# BPU_display-v1d_2-28inch.net
KiCad netlist of a schematic drawn in EAGLE
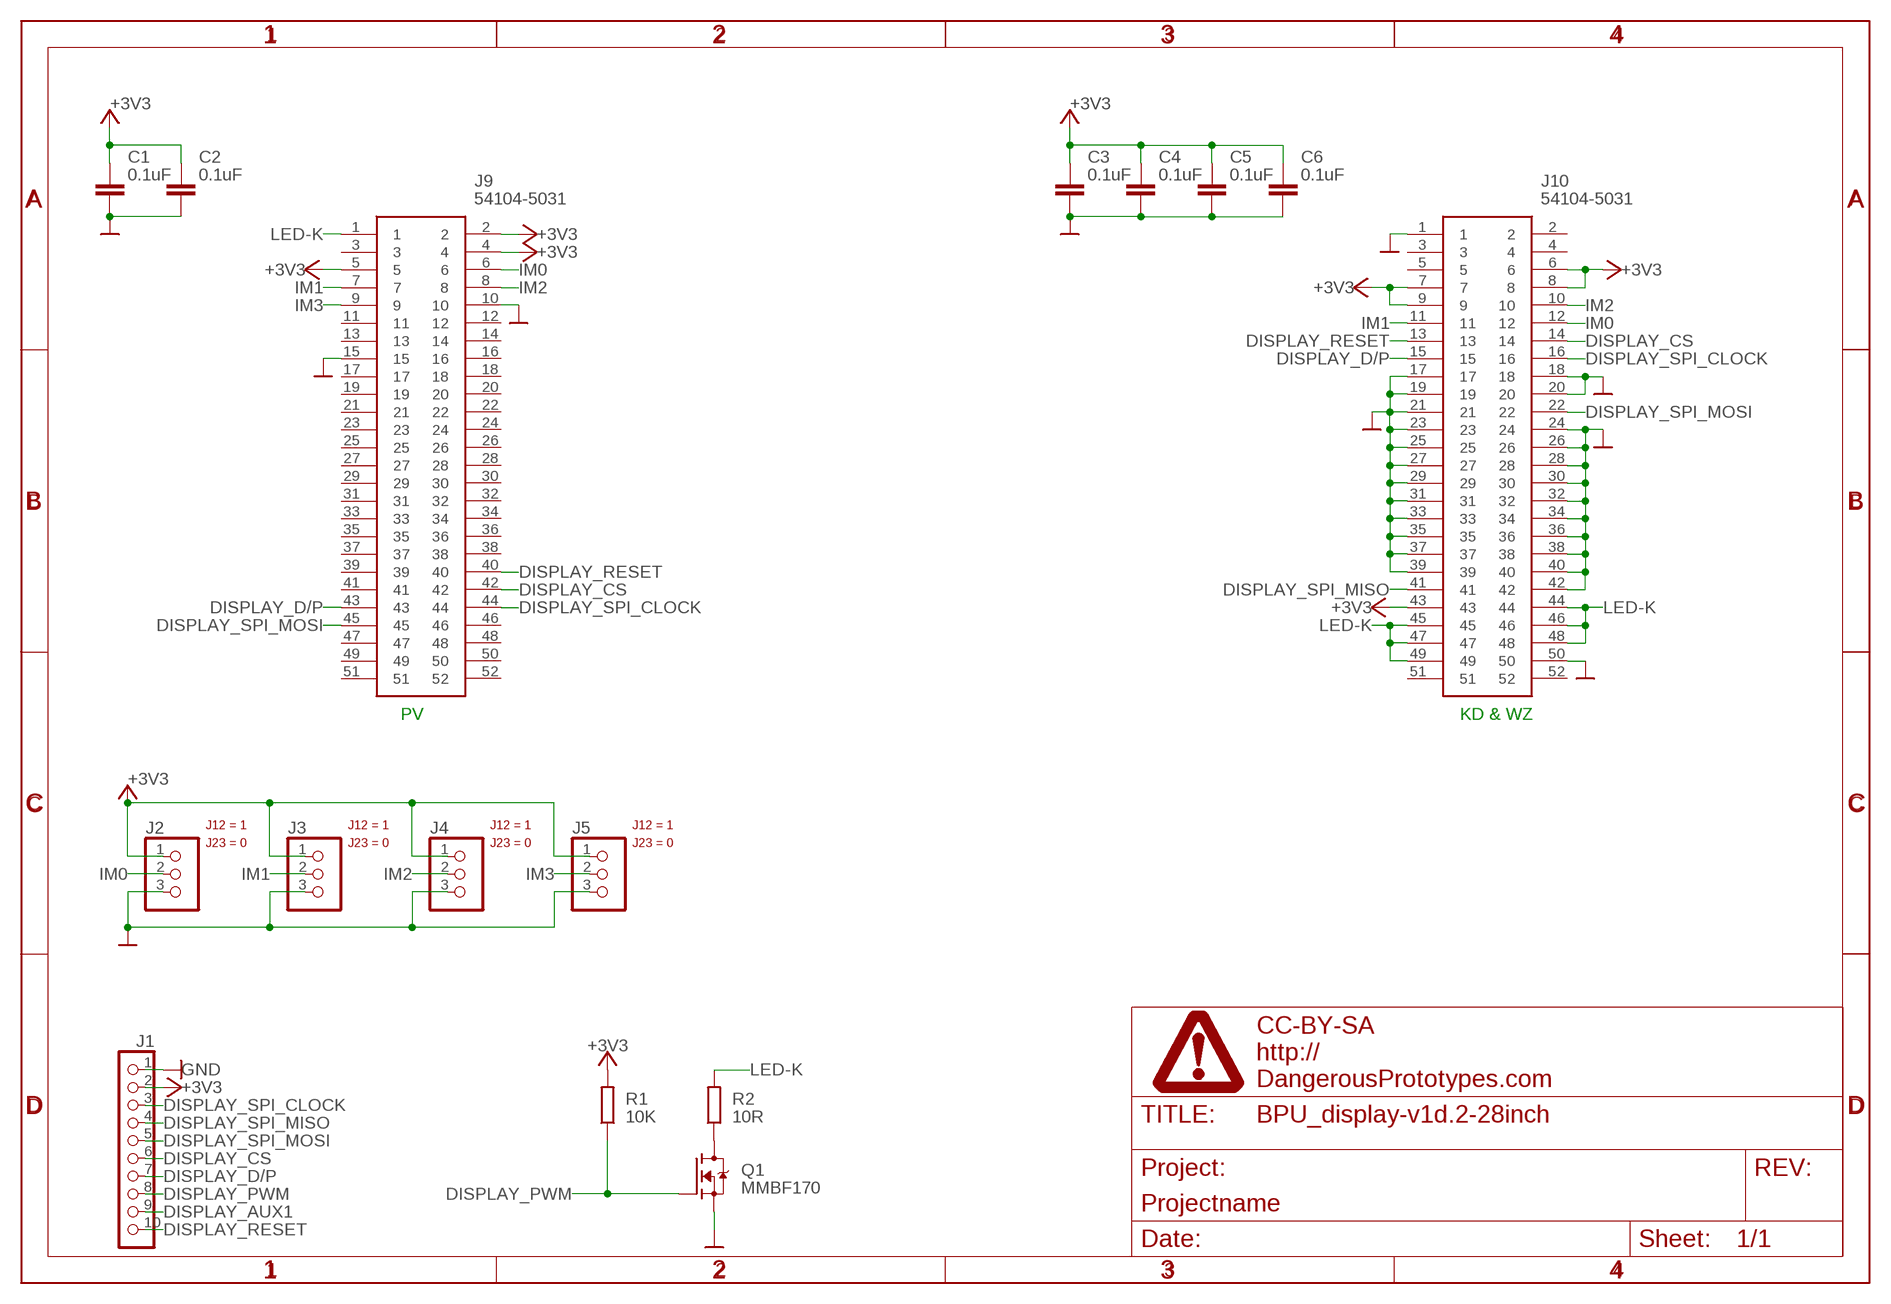
[diagram p0: schematic, sheet 1]

(export (version "E")
  (design (tool "Eeschema 10.0.6"))
  (components
    (comp (ref "C1")
      (value "0.1uF")
      (footprint "eagle-import:C603")
      (libsource (lib "eagle-import") (part "CAPACITOR_NPOL-0603"))
    )
    (comp (ref "C2")
      (value "0.1uF")
      (footprint "eagle-import:C603")
      (libsource (lib "eagle-import") (part "CAPACITOR_NPOL-0603"))
    )
    (comp (ref "C3")
      (value "0.1uF")
      (footprint "eagle-import:C603")
      (libsource (lib "eagle-import") (part "CAPACITOR_NPOL-0603"))
    )
    (comp (ref "C4")
      (value "0.1uF")
      (footprint "eagle-import:C603")
      (libsource (lib "eagle-import") (part "CAPACITOR_NPOL-0603"))
    )
    (comp (ref "C5")
      (value "0.1uF")
      (footprint "eagle-import:C603")
      (libsource (lib "eagle-import") (part "CAPACITOR_NPOL-0603"))
    )
    (comp (ref "C6")
      (value "0.1uF")
      (footprint "eagle-import:C603")
      (libsource (lib "eagle-import") (part "CAPACITOR_NPOL-0603"))
    )
    (comp (ref "J1")
      (value "CON-FPC_X05B20L10T")
      (footprint "eagle-import:X05B20L10T")
      (libsource (lib "eagle-import") (part "CON-FPC_X05B20L10T"))
    )
    (comp (ref "J2")
      (value "JUMPER_1X30805")
      (footprint "eagle-import:JP3_0805")
      (fields
        (field (name "J12") "optA")
        (field (name "J23") "optB")
        (field (name "J12_1") "1")
        (field (name "J23_1") "0")
      )
      (libsource (lib "eagle-import") (part "JUMPER_1X30805"))
    )
    (comp (ref "J3")
      (value "JUMPER_1X30805")
      (footprint "eagle-import:JP3_0805")
      (fields
        (field (name "J12") "optA")
        (field (name "J23") "optB")
        (field (name "J12_1") "1")
        (field (name "J23_1") "0")
      )
      (libsource (lib "eagle-import") (part "JUMPER_1X30805"))
    )
    (comp (ref "J4")
      (value "JUMPER_1X30805")
      (footprint "eagle-import:JP3_0805")
      (fields
        (field (name "J12") "optA")
        (field (name "J23") "optB")
        (field (name "J12_1") "1")
        (field (name "J23_1") "0")
      )
      (libsource (lib "eagle-import") (part "JUMPER_1X30805"))
    )
    (comp (ref "J5")
      (value "JUMPER_1X30805")
      (footprint "eagle-import:JP3_0805")
      (fields
        (field (name "J12") "optA")
        (field (name "J23") "optB")
        (field (name "J12_1") "1")
        (field (name "J23_1") "0")
      )
      (libsource (lib "eagle-import") (part "JUMPER_1X30805"))
    )
    (comp (ref "J9")
      (value "54104-5031")
      (footprint "eagle-import:541045031")
      (fields (field (name "MOUSER_PART_NUMBER") "538-54104-5031"))
      (libsource (lib "eagle-import") (part "54104-5031"))
    )
    (comp (ref "J10")
      (value "54104-5031")
      (footprint "eagle-import:541045031")
      (fields (field (name "MOUSER_PART_NUMBER") "538-54104-5031"))
      (libsource (lib "eagle-import") (part "54104-5031"))
    )
    (comp (ref "PAGE1")
      (value "FRAME_DINA4_L")
      (footprint "eagle-import:DP_LOGO")
      (fields
        (field (name "LICENSE") "CC-BY-SA")
        (field (name "URL1") "http://")
        (field (name "URL2") "DangerousPrototypes.com")
        (field (name "PROJECT") "Projectname")
      )
      (libsource (lib "eagle-import") (part "FRAME_DINA4_L"))
    )
    (comp (ref "Q1")
      (value "MMBF170")
      (footprint "eagle-import:SOT-23")
      (libsource (lib "eagle-import") (part "TRANSISTOR_FET_BS170-SOT-23"))
    )
    (comp (ref "R1")
      (value "10K")
      (footprint "eagle-import:R0603")
      (libsource (lib "eagle-import") (part "R-EU_R0603"))
    )
    (comp (ref "R2")
      (value "10R")
      (footprint "eagle-import:R0603")
      (libsource (lib "eagle-import") (part "R-EU_R0603"))
    )
  )
  (nets
    (net (code "1") (name "/DISPLAY_AUX1") (class "Default")
      (node (ref "J1") (pin "9") (pinfunction "9_9") (pintype "passive"))
    )
    (net (code "2") (name "/DISPLAY_CS") (class "Default")
      (node (ref "J1") (pin "6") (pinfunction "6_6") (pintype "passive"))
      (node (ref "J10") (pin "14") (pinfunction "14_14") (pintype "bidirectional"))
      (node (ref "J9") (pin "42") (pinfunction "42_42") (pintype "bidirectional"))
    )
    (net (code "3") (name "/DISPLAY_D{slash}P") (class "Default")
      (node (ref "J1") (pin "7") (pinfunction "7_7") (pintype "passive"))
      (node (ref "J10") (pin "15") (pinfunction "15_15") (pintype "bidirectional"))
      (node (ref "J9") (pin "43") (pinfunction "43_43") (pintype "bidirectional"))
    )
    (net (code "4") (name "/DISPLAY_PWM") (class "Default")
      (node (ref "J1") (pin "8") (pinfunction "8_8") (pintype "passive"))
      (node (ref "Q1") (pin "1") (pinfunction "G_1") (pintype "passive"))
      (node (ref "R1") (pin "1") (pinfunction "1_1") (pintype "passive"))
    )
    (net (code "5") (name "/DISPLAY_RESET") (class "Default")
      (node (ref "J1") (pin "10") (pinfunction "10_10") (pintype "passive"))
      (node (ref "J10") (pin "13") (pinfunction "13_13") (pintype "bidirectional"))
      (node (ref "J9") (pin "40") (pinfunction "40_40") (pintype "bidirectional"))
    )
    (net (code "6") (name "/DISPLAY_SPI_CLOCK") (class "Default")
      (node (ref "J1") (pin "3") (pinfunction "3_3") (pintype "passive"))
      (node (ref "J10") (pin "16") (pinfunction "16_16") (pintype "bidirectional"))
      (node (ref "J9") (pin "44") (pinfunction "44_44") (pintype "bidirectional"))
    )
    (net (code "7") (name "/DISPLAY_SPI_MISO") (class "Default")
      (node (ref "J1") (pin "4") (pinfunction "4_4") (pintype "passive"))
      (node (ref "J10") (pin "41") (pinfunction "41_41") (pintype "bidirectional"))
    )
    (net (code "8") (name "/DISPLAY_SPI_MOSI") (class "Default")
      (node (ref "J1") (pin "5") (pinfunction "5_5") (pintype "passive"))
      (node (ref "J10") (pin "22") (pinfunction "22_22") (pintype "bidirectional"))
      (node (ref "J9") (pin "45") (pinfunction "45_45") (pintype "bidirectional"))
    )
    (net (code "9") (name "/IM0") (class "Default")
      (node (ref "J10") (pin "12") (pinfunction "12_12") (pintype "bidirectional"))
      (node (ref "J2") (pin "2") (pinfunction "2_2") (pintype "passive"))
      (node (ref "J9") (pin "6") (pinfunction "6_6") (pintype "bidirectional"))
    )
    (net (code "10") (name "/IM1") (class "Default")
      (node (ref "J10") (pin "11") (pinfunction "11_11") (pintype "bidirectional"))
      (node (ref "J3") (pin "2") (pinfunction "2_2") (pintype "passive"))
      (node (ref "J9") (pin "7") (pinfunction "7_7") (pintype "bidirectional"))
    )
    (net (code "11") (name "/IM2") (class "Default")
      (node (ref "J10") (pin "10") (pinfunction "10_10") (pintype "bidirectional"))
      (node (ref "J4") (pin "2") (pinfunction "2_2") (pintype "passive"))
      (node (ref "J9") (pin "8") (pinfunction "8_8") (pintype "bidirectional"))
    )
    (net (code "12") (name "/IM3") (class "Default")
      (node (ref "J5") (pin "2") (pinfunction "2_2") (pintype "passive"))
      (node (ref "J9") (pin "9") (pinfunction "9_9") (pintype "bidirectional"))
    )
    (net (code "13") (name "/LED-K") (class "Default")
      (node (ref "J10") (pin "44") (pinfunction "44_44") (pintype "bidirectional"))
      (node (ref "J10") (pin "45") (pinfunction "45_45") (pintype "bidirectional"))
      (node (ref "J10") (pin "46") (pinfunction "46_46") (pintype "bidirectional"))
      (node (ref "J10") (pin "47") (pinfunction "47_47") (pintype "bidirectional"))
      (node (ref "J10") (pin "48") (pinfunction "48_48") (pintype "bidirectional"))
      (node (ref "J10") (pin "49") (pinfunction "49_49") (pintype "bidirectional"))
      (node (ref "J9") (pin "1") (pinfunction "1_1") (pintype "bidirectional"))
      (node (ref "R2") (pin "2") (pinfunction "2_2") (pintype "passive"))
    )
    (net (code "14") (name "Net-(Q1-D)") (class "Default")
      (node (ref "Q1") (pin "3") (pinfunction "D_3") (pintype "passive"))
      (node (ref "R2") (pin "1") (pinfunction "1_1") (pintype "passive"))
    )
    (net (code "15") (name "SUPPLY_+3V3") (class "Default")
      (node (ref "C1") (pin "1") (pinfunction "1_1") (pintype "passive"))
      (node (ref "C2") (pin "1") (pinfunction "1_1") (pintype "passive"))
      (node (ref "C3") (pin "1") (pinfunction "1_1") (pintype "passive"))
      (node (ref "C4") (pin "1") (pinfunction "1_1") (pintype "passive"))
      (node (ref "C5") (pin "1") (pinfunction "1_1") (pintype "passive"))
      (node (ref "C6") (pin "1") (pinfunction "1_1") (pintype "passive"))
      (node (ref "J1") (pin "2") (pinfunction "2_2") (pintype "passive"))
      (node (ref "J10") (pin "43") (pinfunction "43_43") (pintype "bidirectional"))
      (node (ref "J10") (pin "6") (pinfunction "6_6") (pintype "bidirectional"))
      (node (ref "J10") (pin "7") (pinfunction "7_7") (pintype "bidirectional"))
      (node (ref "J10") (pin "8") (pinfunction "8_8") (pintype "bidirectional"))
      (node (ref "J10") (pin "9") (pinfunction "9_9") (pintype "bidirectional"))
      (node (ref "J2") (pin "1") (pinfunction "1_1") (pintype "passive"))
      (node (ref "J3") (pin "1") (pinfunction "1_1") (pintype "passive"))
      (node (ref "J4") (pin "1") (pinfunction "1_1") (pintype "passive"))
      (node (ref "J5") (pin "1") (pinfunction "1_1") (pintype "passive"))
      (node (ref "J9") (pin "2") (pinfunction "2_2") (pintype "bidirectional"))
      (node (ref "J9") (pin "4") (pinfunction "4_4") (pintype "bidirectional"))
      (node (ref "J9") (pin "5") (pinfunction "5_5") (pintype "bidirectional"))
      (node (ref "R1") (pin "2") (pinfunction "2_2") (pintype "passive"))
    )
    (net (code "16") (name "SUPPLY_GND") (class "Default")
      (node (ref "C1") (pin "2") (pinfunction "2_2") (pintype "passive"))
      (node (ref "C2") (pin "2") (pinfunction "2_2") (pintype "passive"))
      (node (ref "C3") (pin "2") (pinfunction "2_2") (pintype "passive"))
      (node (ref "C4") (pin "2") (pinfunction "2_2") (pintype "passive"))
      (node (ref "C5") (pin "2") (pinfunction "2_2") (pintype "passive"))
      (node (ref "C6") (pin "2") (pinfunction "2_2") (pintype "passive"))
      (node (ref "J1") (pin "1") (pinfunction "1_1") (pintype "passive"))
      (node (ref "J10") (pin "1") (pinfunction "1_1") (pintype "bidirectional"))
      (node (ref "J10") (pin "17") (pinfunction "17_17") (pintype "bidirectional"))
      (node (ref "J10") (pin "18") (pinfunction "18_18") (pintype "bidirectional"))
      (node (ref "J10") (pin "19") (pinfunction "19_19") (pintype "bidirectional"))
      (node (ref "J10") (pin "20") (pinfunction "20_20") (pintype "bidirectional"))
      (node (ref "J10") (pin "21") (pinfunction "21_21") (pintype "bidirectional"))
      (node (ref "J10") (pin "23") (pinfunction "23_23") (pintype "bidirectional"))
      (node (ref "J10") (pin "24") (pinfunction "24_24") (pintype "bidirectional"))
      (node (ref "J10") (pin "25") (pinfunction "25_25") (pintype "bidirectional"))
      (node (ref "J10") (pin "26") (pinfunction "26_26") (pintype "bidirectional"))
      (node (ref "J10") (pin "27") (pinfunction "27_27") (pintype "bidirectional"))
      (node (ref "J10") (pin "28") (pinfunction "28_28") (pintype "bidirectional"))
      (node (ref "J10") (pin "29") (pinfunction "29_29") (pintype "bidirectional"))
      (node (ref "J10") (pin "30") (pinfunction "30_30") (pintype "bidirectional"))
      (node (ref "J10") (pin "31") (pinfunction "31_31") (pintype "bidirectional"))
      (node (ref "J10") (pin "32") (pinfunction "32_32") (pintype "bidirectional"))
      (node (ref "J10") (pin "33") (pinfunction "33_33") (pintype "bidirectional"))
      (node (ref "J10") (pin "34") (pinfunction "34_34") (pintype "bidirectional"))
      (node (ref "J10") (pin "35") (pinfunction "35_35") (pintype "bidirectional"))
      (node (ref "J10") (pin "36") (pinfunction "36_36") (pintype "bidirectional"))
      (node (ref "J10") (pin "37") (pinfunction "37_37") (pintype "bidirectional"))
      (node (ref "J10") (pin "38") (pinfunction "38_38") (pintype "bidirectional"))
      (node (ref "J10") (pin "39") (pinfunction "39_39") (pintype "bidirectional"))
      (node (ref "J10") (pin "40") (pinfunction "40_40") (pintype "bidirectional"))
      (node (ref "J10") (pin "42") (pinfunction "42_42") (pintype "bidirectional"))
      (node (ref "J10") (pin "50") (pinfunction "50_50") (pintype "bidirectional"))
      (node (ref "J2") (pin "3") (pinfunction "3_3") (pintype "passive"))
      (node (ref "J3") (pin "3") (pinfunction "3_3") (pintype "passive"))
      (node (ref "J4") (pin "3") (pinfunction "3_3") (pintype "passive"))
      (node (ref "J5") (pin "3") (pinfunction "3_3") (pintype "passive"))
      (node (ref "J9") (pin "10") (pinfunction "10_10") (pintype "bidirectional"))
      (node (ref "J9") (pin "15") (pinfunction "15_15") (pintype "bidirectional"))
      (node (ref "Q1") (pin "2") (pinfunction "S_2") (pintype "passive"))
    )
    (net (code "17") (name "unconnected-(J9-Pad3)") (class "Default")
      (node (ref "J9") (pin "3") (pinfunction "3_3") (pintype "bidirectional"))
    )
    (net (code "18") (name "unconnected-(J9-Pad11)") (class "Default")
      (node (ref "J9") (pin "11") (pinfunction "11_11") (pintype "bidirectional"))
    )
    (net (code "19") (name "unconnected-(J9-Pad12)") (class "Default")
      (node (ref "J9") (pin "12") (pinfunction "12_12") (pintype "bidirectional"))
    )
    (net (code "20") (name "unconnected-(J9-Pad13)") (class "Default")
      (node (ref "J9") (pin "13") (pinfunction "13_13") (pintype "bidirectional"))
    )
    (net (code "21") (name "unconnected-(J9-Pad14)") (class "Default")
      (node (ref "J9") (pin "14") (pinfunction "14_14") (pintype "bidirectional"))
    )
    (net (code "22") (name "unconnected-(J9-Pad16)") (class "Default")
      (node (ref "J9") (pin "16") (pinfunction "16_16") (pintype "bidirectional"))
    )
    (net (code "23") (name "unconnected-(J9-Pad17)") (class "Default")
      (node (ref "J9") (pin "17") (pinfunction "17_17") (pintype "bidirectional"))
    )
    (net (code "24") (name "unconnected-(J9-Pad18)") (class "Default")
      (node (ref "J9") (pin "18") (pinfunction "18_18") (pintype "bidirectional"))
    )
    (net (code "25") (name "unconnected-(J9-Pad19)") (class "Default")
      (node (ref "J9") (pin "19") (pinfunction "19_19") (pintype "bidirectional"))
    )
    (net (code "26") (name "unconnected-(J9-Pad20)") (class "Default")
      (node (ref "J9") (pin "20") (pinfunction "20_20") (pintype "bidirectional"))
    )
    (net (code "27") (name "unconnected-(J9-Pad21)") (class "Default")
      (node (ref "J9") (pin "21") (pinfunction "21_21") (pintype "bidirectional"))
    )
    (net (code "28") (name "unconnected-(J9-Pad22)") (class "Default")
      (node (ref "J9") (pin "22") (pinfunction "22_22") (pintype "bidirectional"))
    )
    (net (code "29") (name "unconnected-(J9-Pad23)") (class "Default")
      (node (ref "J9") (pin "23") (pinfunction "23_23") (pintype "bidirectional"))
    )
    (net (code "30") (name "unconnected-(J9-Pad24)") (class "Default")
      (node (ref "J9") (pin "24") (pinfunction "24_24") (pintype "bidirectional"))
    )
    (net (code "31") (name "unconnected-(J9-Pad25)") (class "Default")
      (node (ref "J9") (pin "25") (pinfunction "25_25") (pintype "bidirectional"))
    )
    (net (code "32") (name "unconnected-(J9-Pad26)") (class "Default")
      (node (ref "J9") (pin "26") (pinfunction "26_26") (pintype "bidirectional"))
    )
    (net (code "33") (name "unconnected-(J9-Pad27)") (class "Default")
      (node (ref "J9") (pin "27") (pinfunction "27_27") (pintype "bidirectional"))
    )
    (net (code "34") (name "unconnected-(J9-Pad28)") (class "Default")
      (node (ref "J9") (pin "28") (pinfunction "28_28") (pintype "bidirectional"))
    )
    (net (code "35") (name "unconnected-(J9-Pad29)") (class "Default")
      (node (ref "J9") (pin "29") (pinfunction "29_29") (pintype "bidirectional"))
    )
    (net (code "36") (name "unconnected-(J9-Pad30)") (class "Default")
      (node (ref "J9") (pin "30") (pinfunction "30_30") (pintype "bidirectional"))
    )
    (net (code "37") (name "unconnected-(J9-Pad31)") (class "Default")
      (node (ref "J9") (pin "31") (pinfunction "31_31") (pintype "bidirectional"))
    )
    (net (code "38") (name "unconnected-(J9-Pad32)") (class "Default")
      (node (ref "J9") (pin "32") (pinfunction "32_32") (pintype "bidirectional"))
    )
    (net (code "39") (name "unconnected-(J9-Pad33)") (class "Default")
      (node (ref "J9") (pin "33") (pinfunction "33_33") (pintype "bidirectional"))
    )
    (net (code "40") (name "unconnected-(J9-Pad34)") (class "Default")
      (node (ref "J9") (pin "34") (pinfunction "34_34") (pintype "bidirectional"))
    )
    (net (code "41") (name "unconnected-(J9-Pad35)") (class "Default")
      (node (ref "J9") (pin "35") (pinfunction "35_35") (pintype "bidirectional"))
    )
    (net (code "42") (name "unconnected-(J9-Pad36)") (class "Default")
      (node (ref "J9") (pin "36") (pinfunction "36_36") (pintype "bidirectional"))
    )
    (net (code "43") (name "unconnected-(J9-Pad37)") (class "Default")
      (node (ref "J9") (pin "37") (pinfunction "37_37") (pintype "bidirectional"))
    )
    (net (code "44") (name "unconnected-(J9-Pad38)") (class "Default")
      (node (ref "J9") (pin "38") (pinfunction "38_38") (pintype "bidirectional"))
    )
    (net (code "45") (name "unconnected-(J9-Pad39)") (class "Default")
      (node (ref "J9") (pin "39") (pinfunction "39_39") (pintype "bidirectional"))
    )
    (net (code "46") (name "unconnected-(J9-Pad41)") (class "Default")
      (node (ref "J9") (pin "41") (pinfunction "41_41") (pintype "bidirectional"))
    )
    (net (code "47") (name "unconnected-(J9-Pad46)") (class "Default")
      (node (ref "J9") (pin "46") (pinfunction "46_46") (pintype "bidirectional"))
    )
    (net (code "48") (name "unconnected-(J9-Pad47)") (class "Default")
      (node (ref "J9") (pin "47") (pinfunction "47_47") (pintype "bidirectional"))
    )
    (net (code "49") (name "unconnected-(J9-Pad48)") (class "Default")
      (node (ref "J9") (pin "48") (pinfunction "48_48") (pintype "bidirectional"))
    )
    (net (code "50") (name "unconnected-(J9-Pad49)") (class "Default")
      (node (ref "J9") (pin "49") (pinfunction "49_49") (pintype "bidirectional"))
    )
    (net (code "51") (name "unconnected-(J9-Pad50)") (class "Default")
      (node (ref "J9") (pin "50") (pinfunction "50_50") (pintype "bidirectional"))
    )
    (net (code "52") (name "unconnected-(J9-Pad51)") (class "Default")
      (node (ref "J9") (pin "51") (pinfunction "51_51") (pintype "bidirectional"))
    )
    (net (code "53") (name "unconnected-(J9-Pad52)") (class "Default")
      (node (ref "J9") (pin "52") (pinfunction "52_52") (pintype "bidirectional"))
    )
    (net (code "54") (name "unconnected-(J10-Pad2)") (class "Default")
      (node (ref "J10") (pin "2") (pinfunction "2_2") (pintype "bidirectional"))
    )
    (net (code "55") (name "unconnected-(J10-Pad3)") (class "Default")
      (node (ref "J10") (pin "3") (pinfunction "3_3") (pintype "bidirectional"))
    )
    (net (code "56") (name "unconnected-(J10-Pad4)") (class "Default")
      (node (ref "J10") (pin "4") (pinfunction "4_4") (pintype "bidirectional"))
    )
    (net (code "57") (name "unconnected-(J10-Pad5)") (class "Default")
      (node (ref "J10") (pin "5") (pinfunction "5_5") (pintype "bidirectional"))
    )
    (net (code "58") (name "unconnected-(J10-Pad51)") (class "Default")
      (node (ref "J10") (pin "51") (pinfunction "51_51") (pintype "bidirectional"))
    )
    (net (code "59") (name "unconnected-(J10-Pad52)") (class "Default")
      (node (ref "J10") (pin "52") (pinfunction "52_52") (pintype "bidirectional"))
    )
  )
)
